# Power.net
KiCad netlist of a schematic drawn in Altium Designer
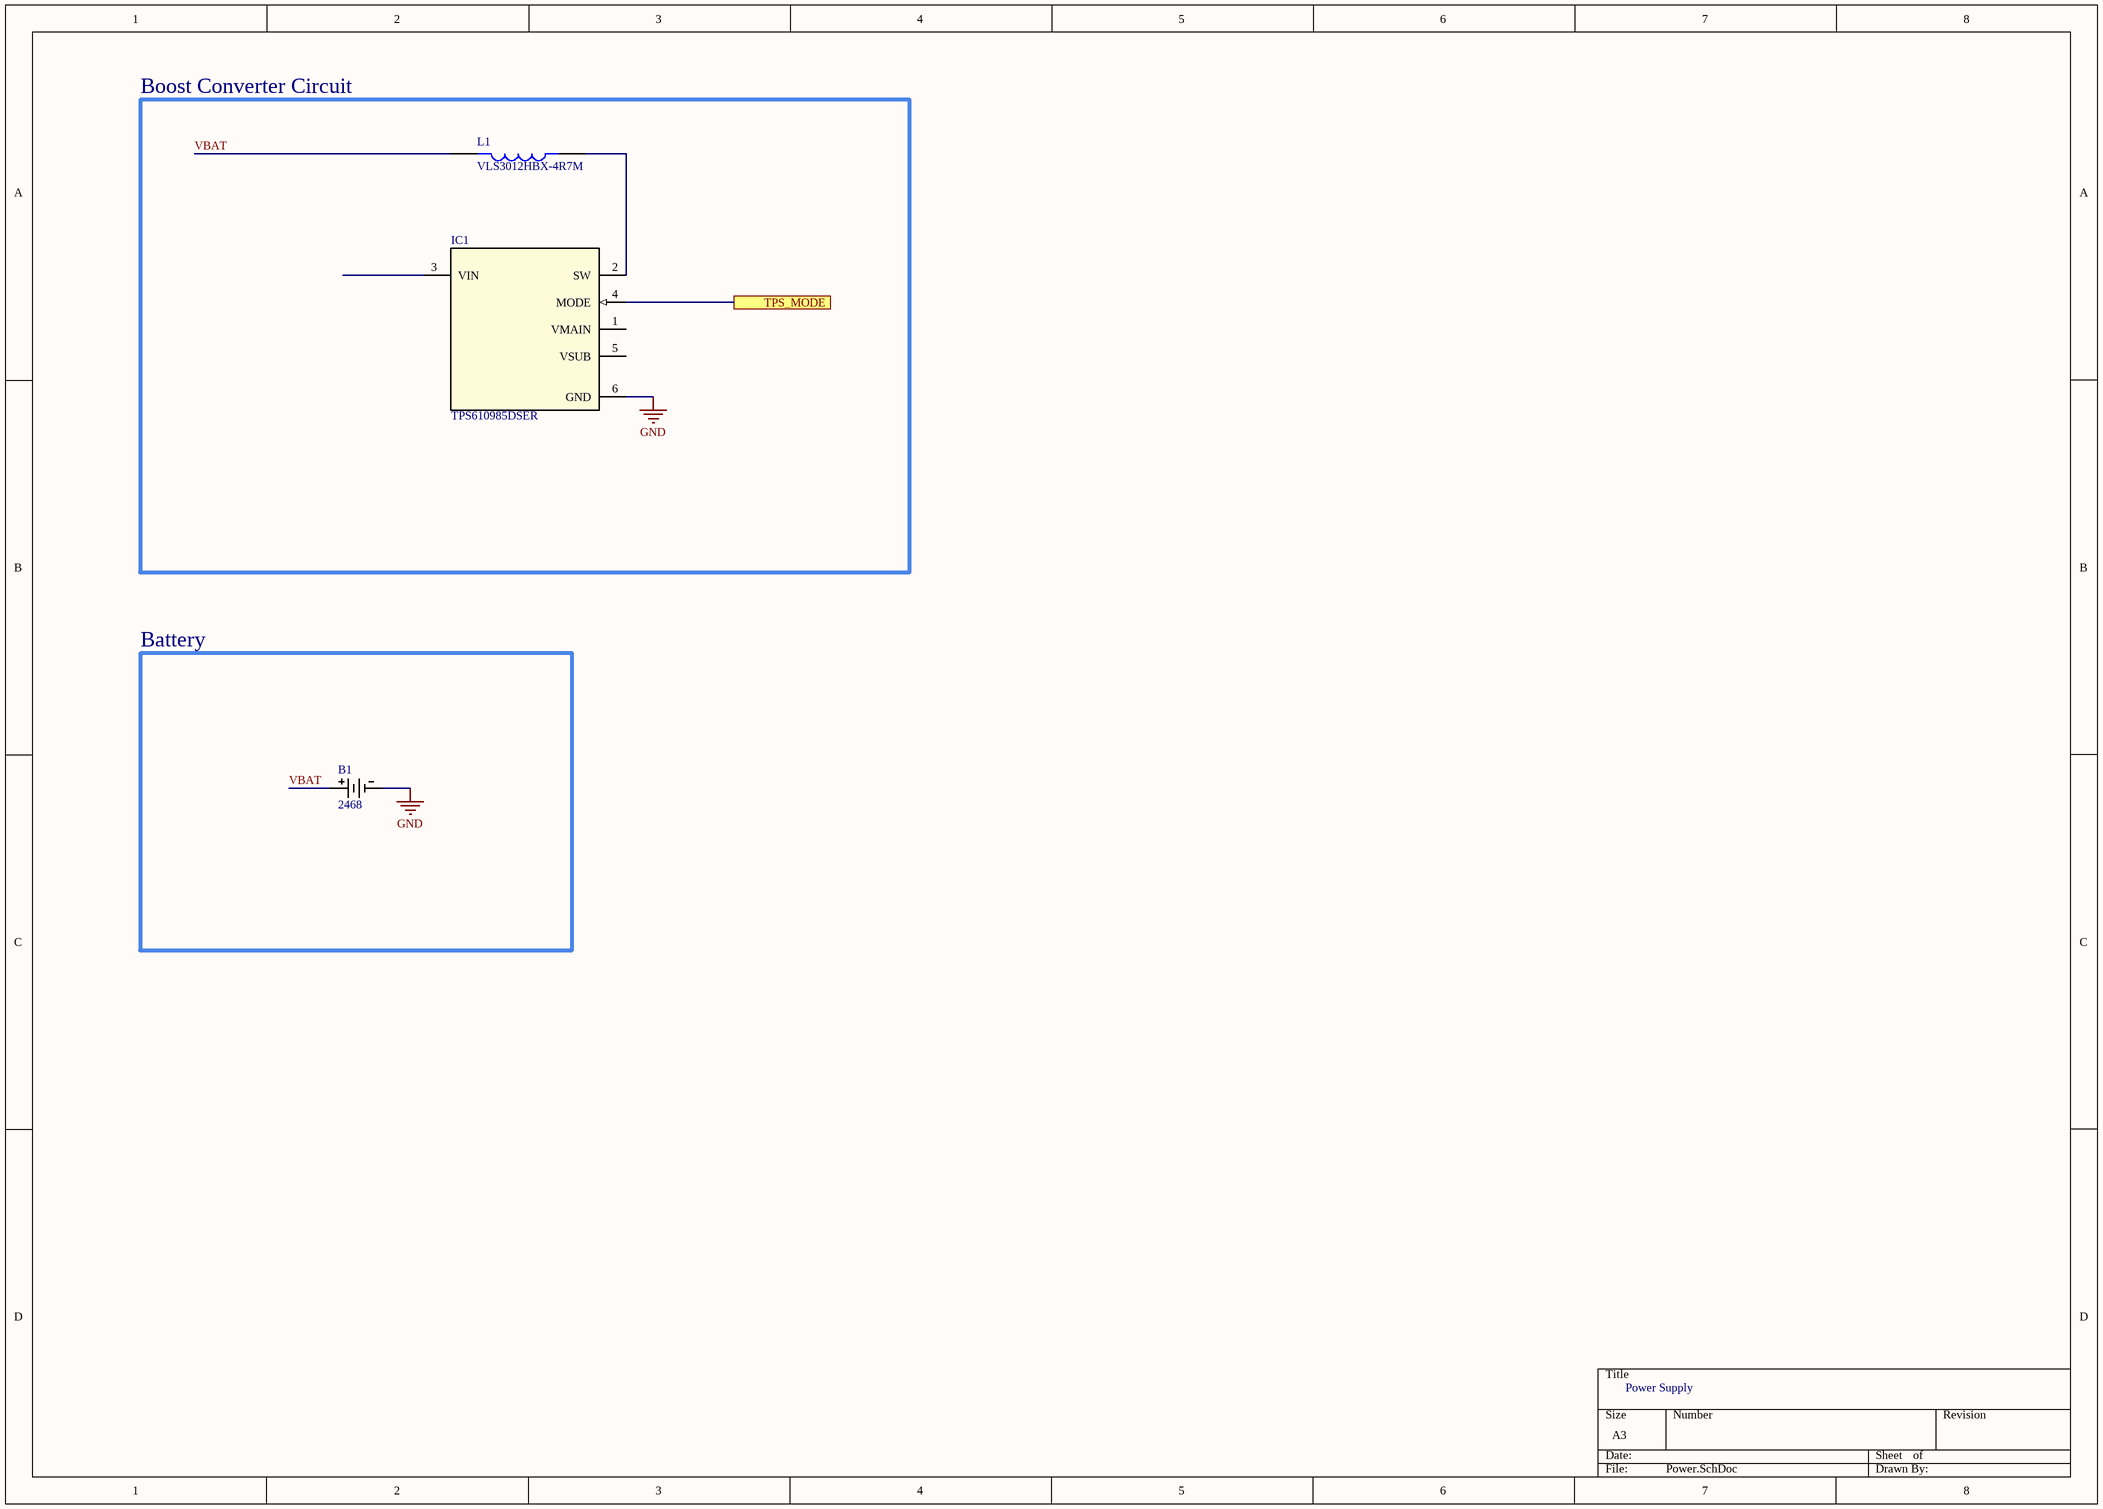
[diagram p0: Power.SchDoc]

(export (version "E")
  (design (tool "Eeschema 10.0.6"))
  (components
    (comp (ref "B1")
      (value "2468")
      (footprint "2468_KEY")
      (description "No Description Available")
      (libsource (lib "Schlib1") (part "2468"))
    )
    (comp (ref "IC1")
      (value "TPS610985DSER")
      (description "No Description Available")
      (libsource (lib "Schlib1") (part "TPS610985DSER"))
    )
    (comp (ref "L1")
      (value "VLS3012HBX-4R7M")
      (footprint "IND_VLS3012HBX-4R7M")
      (description "4.7 µH Shielded Drum Core, Wirewound Inductor 2.23 A 201mOhm Max Nonstandard -")
      (fields (field (name "MF") "TDK"))
      (libsource (lib "TPS610985DSER") (part "VLS3012HBX-4R7M"))
    )
  )
  (nets
    (net (code "1") (name "/TPS_MODE") (class "Default")
      (node (ref "IC1") (pin "4") (pinfunction "MODE_4") (pintype "input"))
    )
    (net (code "2") (name "/VBAT") (class "Default")
      (node (ref "B1") (pin "1") (pinfunction "1_1") (pintype "passive"))
      (node (ref "L1") (pin "2") (pinfunction "2_2") (pintype "passive"))
    )
    (net (code "3") (name "GND") (class "Default")
      (node (ref "B1") (pin "2") (pinfunction "2_2") (pintype "passive"))
      (node (ref "IC1") (pin "6") (pinfunction "GND_6") (pintype "power_in"))
    )
    (net (code "4") (name "Net-(IC1-SW)") (class "Default")
      (node (ref "IC1") (pin "2") (pinfunction "SW_2") (pintype "power_in"))
      (node (ref "L1") (pin "1") (pinfunction "1_1") (pintype "passive"))
    )
    (net (code "5") (name "unconnected-(IC1-VIN-Pad3)") (class "Default")
      (node (ref "IC1") (pin "3") (pinfunction "VIN_3") (pintype "power_in"))
    )
    (net (code "6") (name "unconnected-(IC1-VMAIN-Pad1)") (class "Default")
      (node (ref "IC1") (pin "1") (pinfunction "VMAIN_1") (pintype "power_in"))
    )
    (net (code "7") (name "unconnected-(IC1-VSUB-Pad5)") (class "Default")
      (node (ref "IC1") (pin "5") (pinfunction "VSUB_5") (pintype "power_in"))
    )
  )
)
